# Buttons.net
KiCad netlist of a schematic drawn in Altium Designer
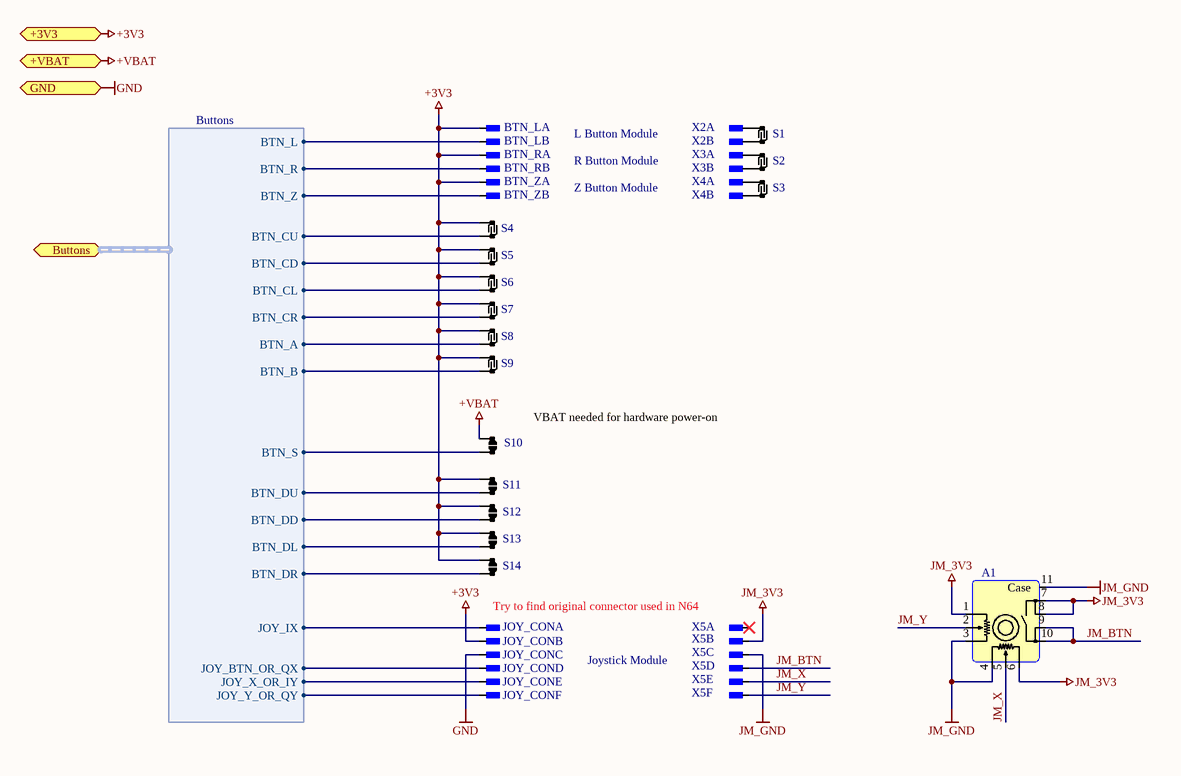
[diagram p0: Buttons.SchDoc]

(export (version "E")
  (design (tool "Eeschema 10.0.6"))
  (components
    (comp (ref "A1")
      (value "A_JOYSTICK_MODULE_RKJXK122400Y")
      (footprint "A_JOYSTICK_MODULE_RKJXK122400Y")
      (libsource (lib "AM") (part "A_JOYSTICK_MODULE_RKJXK122400Y"))
    )
    (comp (ref "BTN_L")
      (value "X_CONNECTOR_P2.54_D0.9_1X2")
      (footprint "THT_CON_P2.54_D0.9_1X2")
      (description "Pitch 2.54, Diameter 0.9mm, 1 row, 2 columns")
      (libsource (lib "") (part "X_CONNECTOR_P2.54_D0.9_1X2_1"))
    )
    (comp (ref "BTN_R")
      (value "X_CONNECTOR_P2.54_D0.9_1X2")
      (footprint "THT_CON_P2.54_D0.9_1X2")
      (description "Pitch 2.54, Diameter 0.9mm, 1 row, 2 columns")
      (libsource (lib "") (part "X_CONNECTOR_P2.54_D0.9_1X2_1"))
    )
    (comp (ref "BTN_Z")
      (value "X_CONNECTOR_P2.54_D0.9_1X2")
      (footprint "THT_CON_P2.54_D0.9_1X2")
      (description "Pitch 2.54, Diameter 0.9mm, 1 row, 2 columns")
      (libsource (lib "") (part "X_CONNECTOR_P2.54_D0.9_1X2_1"))
    )
    (comp (ref "JOY_CON")
      (value "X_CONNECTOR_P2.54_D0.9_1X6")
      (footprint "THT_CON_P2.54_D0.9_1X6")
      (description "Pitch 2.54, Diameter 0.9mm, 1 row, 6 columns")
      (libsource (lib "AM") (part "X_CONNECTOR_P2.54_D0.9_1X6"))
    )
    (comp (ref "S1")
      (value "S_N64_FINGER_CARBON_CONTACT")
      (footprint "SMD_N64_FINGER_CARBON_CONTACT")
      (description "N64 DPAD Carbon ink contact")
      (libsource (lib "AM") (part "S_N64_FINGER_CARBON_CONTACT"))
    )
    (comp (ref "S2")
      (value "S_N64_FINGER_CARBON_CONTACT")
      (footprint "SMD_N64_FINGER_CARBON_CONTACT")
      (description "N64 DPAD Carbon ink contact")
      (libsource (lib "AM") (part "S_N64_FINGER_CARBON_CONTACT"))
    )
    (comp (ref "S3")
      (value "S_N64_FINGER_CARBON_CONTACT")
      (footprint "SMD_N64_FINGER_CARBON_CONTACT")
      (description "N64 DPAD Carbon ink contact")
      (libsource (lib "AM") (part "S_N64_FINGER_CARBON_CONTACT"))
    )
    (comp (ref "S4")
      (value "S_N64_FINGER_CARBON_CONTACT")
      (footprint "SMD_N64_FINGER_CARBON_CONTACT")
      (description "N64 DPAD Carbon ink contact")
      (libsource (lib "AM") (part "S_N64_FINGER_CARBON_CONTACT"))
    )
    (comp (ref "S5")
      (value "S_N64_FINGER_CARBON_CONTACT")
      (footprint "SMD_N64_FINGER_CARBON_CONTACT")
      (description "N64 DPAD Carbon ink contact")
      (libsource (lib "AM") (part "S_N64_FINGER_CARBON_CONTACT"))
    )
    (comp (ref "S6")
      (value "S_N64_FINGER_CARBON_CONTACT")
      (footprint "SMD_N64_FINGER_CARBON_CONTACT")
      (description "N64 DPAD Carbon ink contact")
      (libsource (lib "AM") (part "S_N64_FINGER_CARBON_CONTACT"))
    )
    (comp (ref "S7")
      (value "S_N64_FINGER_CARBON_CONTACT")
      (footprint "SMD_N64_FINGER_CARBON_CONTACT")
      (description "N64 DPAD Carbon ink contact")
      (libsource (lib "AM") (part "S_N64_FINGER_CARBON_CONTACT"))
    )
    (comp (ref "S8")
      (value "S_N64_FINGER_CARBON_CONTACT")
      (footprint "SMD_N64_FINGER_CARBON_CONTACT")
      (description "N64 DPAD Carbon ink contact")
      (libsource (lib "AM") (part "S_N64_FINGER_CARBON_CONTACT"))
    )
    (comp (ref "S9")
      (value "S_N64_FINGER_CARBON_CONTACT")
      (footprint "SMD_N64_FINGER_CARBON_CONTACT")
      (description "N64 DPAD Carbon ink contact")
      (libsource (lib "AM") (part "S_N64_FINGER_CARBON_CONTACT"))
    )
    (comp (ref "S10")
      (value "S_N64_START_CARBON_CONTACT")
      (footprint "SMD_N64_START_CARBON_CONTACT")
      (description "N64 DPAD Carbon ink contact")
      (libsource (lib "AM") (part "S_N64_START_CARBON_CONTACT"))
    )
    (comp (ref "S11")
      (value "S_N64_DPAD_CARBON_CONTACT")
      (footprint "SMD_N64_DPAD_CARBON_CONTACT")
      (description "N64 DPAD Carbon ink contact")
      (libsource (lib "AM") (part "S_N64_DPAD_CARBON_CONTACT"))
    )
    (comp (ref "S12")
      (value "S_N64_DPAD_CARBON_CONTACT")
      (footprint "SMD_N64_DPAD_CARBON_CONTACT")
      (description "N64 DPAD Carbon ink contact")
      (libsource (lib "AM") (part "S_N64_DPAD_CARBON_CONTACT"))
    )
    (comp (ref "S13")
      (value "S_N64_DPAD_CARBON_CONTACT")
      (footprint "SMD_N64_DPAD_CARBON_CONTACT")
      (description "N64 DPAD Carbon ink contact")
      (libsource (lib "AM") (part "S_N64_DPAD_CARBON_CONTACT"))
    )
    (comp (ref "S14")
      (value "S_N64_DPAD_CARBON_CONTACT")
      (footprint "SMD_N64_DPAD_CARBON_CONTACT")
      (description "N64 DPAD Carbon ink contact")
      (libsource (lib "AM") (part "S_N64_DPAD_CARBON_CONTACT"))
    )
    (comp (ref "X2")
      (value "X_CONNECTOR_P2.54_D0.9_1X2")
      (footprint "THT_CON_P2.54_D0.9_1X2")
      (description "Pitch 2.54, Diameter 0.9mm, 1 row, 2 columns")
      (libsource (lib "AM") (part "X_CONNECTOR_P2.54_D0.9_1X2"))
    )
    (comp (ref "X3")
      (value "X_CONNECTOR_P2.54_D0.9_1X2")
      (footprint "THT_CON_P2.54_D0.9_1X2")
      (description "Pitch 2.54, Diameter 0.9mm, 1 row, 2 columns")
      (libsource (lib "AM") (part "X_CONNECTOR_P2.54_D0.9_1X2"))
    )
    (comp (ref "X4")
      (value "X_CONNECTOR_P2.54_D0.9_1X2")
      (footprint "THT_CON_P2.54_D0.9_1X2")
      (description "Pitch 2.54, Diameter 0.9mm, 1 row, 2 columns")
      (libsource (lib "AM") (part "X_CONNECTOR_P2.54_D0.9_1X2"))
    )
    (comp (ref "X5")
      (value "X_CONNECTOR_P2.54_D0.9_2X3")
      (footprint "THT_CON_P2.54_D0.9_2X3")
      (description "Pitch 2.54, Diameter 0.9mm, 2 row, 3 columns")
      (libsource (lib "AM") (part "X_CONNECTOR_P2.54_D0.9_2X3"))
    )
  )
  (nets
    (net (code "2") (name "+3V3") (class "Default")
      (node (ref "BTN_L") (pin "1") (pinfunction "1_1") (pintype "passive"))
      (node (ref "BTN_R") (pin "1") (pinfunction "1_1") (pintype "passive"))
      (node (ref "BTN_Z") (pin "1") (pinfunction "1_1") (pintype "passive"))
      (node (ref "JOY_CON") (pin "2") (pinfunction "2_2") (pintype "passive"))
      (node (ref "S11") (pin "1") (pinfunction "1_1") (pintype "passive"))
      (node (ref "S12") (pin "1") (pinfunction "1_1") (pintype "passive"))
      (node (ref "S13") (pin "1") (pinfunction "1_1") (pintype "passive"))
      (node (ref "S14") (pin "1") (pinfunction "1_1") (pintype "passive"))
      (node (ref "S4") (pin "1") (pinfunction "1_1") (pintype "passive"))
      (node (ref "S5") (pin "1") (pinfunction "1_1") (pintype "passive"))
      (node (ref "S6") (pin "1") (pinfunction "1_1") (pintype "passive"))
      (node (ref "S7") (pin "1") (pinfunction "1_1") (pintype "passive"))
      (node (ref "S8") (pin "1") (pinfunction "1_1") (pintype "passive"))
      (node (ref "S9") (pin "1") (pinfunction "1_1") (pintype "passive"))
    )
    (net (code "3") (name "+VBAT") (class "Default")
      (node (ref "S10") (pin "1") (pinfunction "1_1") (pintype "passive"))
    )
    (net (code "4") (name "/BTN_A") (class "Default")
      (node (ref "S8") (pin "2") (pinfunction "2_2") (pintype "passive"))
    )
    (net (code "5") (name "/BTN_B") (class "Default")
      (node (ref "S9") (pin "2") (pinfunction "2_2") (pintype "passive"))
    )
    (net (code "6") (name "/BTN_CD") (class "Default")
      (node (ref "S5") (pin "2") (pinfunction "2_2") (pintype "passive"))
    )
    (net (code "7") (name "/BTN_CL") (class "Default")
      (node (ref "S6") (pin "2") (pinfunction "2_2") (pintype "passive"))
    )
    (net (code "8") (name "/BTN_CR") (class "Default")
      (node (ref "S7") (pin "2") (pinfunction "2_2") (pintype "passive"))
    )
    (net (code "9") (name "/BTN_CU") (class "Default")
      (node (ref "S4") (pin "2") (pinfunction "2_2") (pintype "passive"))
    )
    (net (code "10") (name "/BTN_DD") (class "Default")
      (node (ref "S12") (pin "2") (pinfunction "2_2") (pintype "passive"))
    )
    (net (code "11") (name "/BTN_DL") (class "Default")
      (node (ref "S13") (pin "2") (pinfunction "2_2") (pintype "passive"))
    )
    (net (code "12") (name "/BTN_DR") (class "Default")
      (node (ref "S14") (pin "2") (pinfunction "2_2") (pintype "passive"))
    )
    (net (code "13") (name "/BTN_DU") (class "Default")
      (node (ref "S11") (pin "2") (pinfunction "2_2") (pintype "passive"))
    )
    (net (code "14") (name "/BTN_L") (class "Default")
      (node (ref "BTN_L") (pin "2") (pinfunction "2_2") (pintype "passive"))
    )
    (net (code "15") (name "/BTN_R") (class "Default")
      (node (ref "BTN_R") (pin "2") (pinfunction "2_2") (pintype "passive"))
    )
    (net (code "16") (name "/BTN_S") (class "Default")
      (node (ref "S10") (pin "2") (pinfunction "2_2") (pintype "passive"))
    )
    (net (code "17") (name "/BTN_Z") (class "Default")
      (node (ref "BTN_Z") (pin "2") (pinfunction "2_2") (pintype "passive"))
    )
    (net (code "18") (name "/JM_BTN") (class "Default")
      (node (ref "A1") (pin "10") (pinfunction "BTN-_10") (pintype "passive"))
      (node (ref "A1") (pin "9") (pinfunction "BTN-_9") (pintype "passive"))
      (node (ref "X5") (pin "4") (pinfunction "4_4") (pintype "passive"))
    )
    (net (code "19") (name "/JM_X") (class "Default")
      (node (ref "A1") (pin "5") (pinfunction "Y_5") (pintype "passive"))
      (node (ref "X5") (pin "5") (pinfunction "5_5") (pintype "passive"))
    )
    (net (code "20") (name "/JM_Y") (class "Default")
      (node (ref "A1") (pin "2") (pinfunction "X_2") (pintype "passive"))
      (node (ref "X5") (pin "6") (pinfunction "6_6") (pintype "passive"))
    )
    (net (code "21") (name "/JOY_BTN_OR_QX") (class "Default")
      (node (ref "JOY_CON") (pin "4") (pinfunction "4_4") (pintype "passive"))
    )
    (net (code "22") (name "/JOY_IX") (class "Default")
      (node (ref "JOY_CON") (pin "1") (pinfunction "1_1") (pintype "passive"))
    )
    (net (code "23") (name "/JOY_X_OR_IY") (class "Default")
      (node (ref "JOY_CON") (pin "5") (pinfunction "5_5") (pintype "passive"))
    )
    (net (code "24") (name "/JOY_Y_OR_QY") (class "Default")
      (node (ref "JOY_CON") (pin "6") (pinfunction "6_6") (pintype "passive"))
    )
    (net (code "26") (name "GND") (class "Default")
      (node (ref "JOY_CON") (pin "3") (pinfunction "3_3") (pintype "passive"))
    )
    (net (code "27") (name "JM_3V3") (class "Default")
      (node (ref "A1") (pin "1") (pinfunction "XV+_1") (pintype "passive"))
      (node (ref "A1") (pin "6") (pinfunction "YV-_6") (pintype "passive"))
      (node (ref "A1") (pin "7") (pinfunction "BTN+_7") (pintype "passive"))
      (node (ref "A1") (pin "8") (pinfunction "BTN+_8") (pintype "passive"))
      (node (ref "X5") (pin "2") (pinfunction "2_2") (pintype "passive"))
    )
    (net (code "28") (name "JM_GND") (class "Default")
      (node (ref "A1") (pin "11") (pinfunction "Case_11") (pintype "passive"))
      (node (ref "A1") (pin "3") (pinfunction "XV-_3") (pintype "passive"))
      (node (ref "A1") (pin "4") (pinfunction "YV+_4") (pintype "passive"))
      (node (ref "X5") (pin "3") (pinfunction "3_3") (pintype "passive"))
    )
    (net (code "29") (name "Net-(S1-Pad1)") (class "Default")
      (node (ref "S1") (pin "1") (pinfunction "1_1") (pintype "passive"))
      (node (ref "X2") (pin "1") (pinfunction "1_1") (pintype "passive"))
    )
    (net (code "30") (name "Net-(S1-Pad2)") (class "Default")
      (node (ref "S1") (pin "2") (pinfunction "2_2") (pintype "passive"))
      (node (ref "X2") (pin "2") (pinfunction "2_2") (pintype "passive"))
    )
    (net (code "31") (name "Net-(S2-Pad1)") (class "Default")
      (node (ref "S2") (pin "1") (pinfunction "1_1") (pintype "passive"))
      (node (ref "X3") (pin "1") (pinfunction "1_1") (pintype "passive"))
    )
    (net (code "32") (name "Net-(S2-Pad2)") (class "Default")
      (node (ref "S2") (pin "2") (pinfunction "2_2") (pintype "passive"))
      (node (ref "X3") (pin "2") (pinfunction "2_2") (pintype "passive"))
    )
    (net (code "33") (name "Net-(S3-Pad1)") (class "Default")
      (node (ref "S3") (pin "1") (pinfunction "1_1") (pintype "passive"))
      (node (ref "X4") (pin "1") (pinfunction "1_1") (pintype "passive"))
    )
    (net (code "34") (name "Net-(S3-Pad2)") (class "Default")
      (node (ref "S3") (pin "2") (pinfunction "2_2") (pintype "passive"))
      (node (ref "X4") (pin "2") (pinfunction "2_2") (pintype "passive"))
    )
    (net (code "35") (name "unconnected-(X5-Pad1)") (class "Default")
      (node (ref "X5") (pin "1") (pinfunction "1_1") (pintype "passive+no_connect"))
    )
  )
)
